# 220V-12V_Power_Interface.net
KiCad netlist of a schematic drawn in Altium Designer
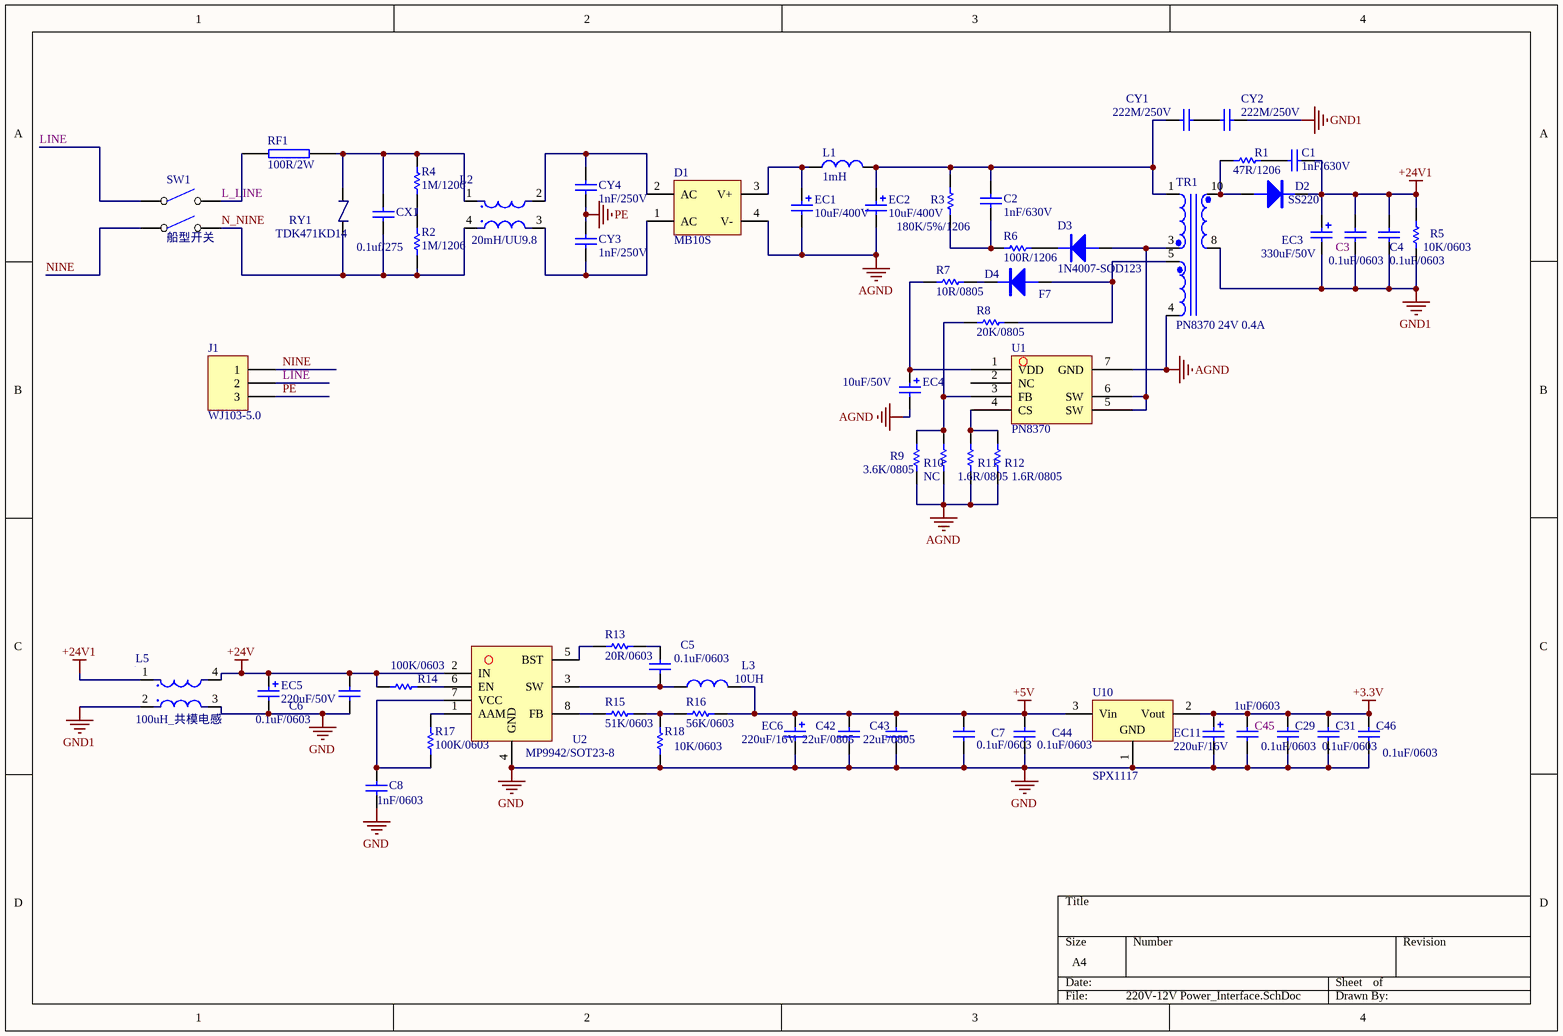
[diagram p0: 220V-12V Power_Interface.SchDoc]

(export (version "E")
  (design (tool "Eeschema 10.0.6"))
  (components
    (comp (ref "C1")
      (value "1nF/630V")
      (footprint "CAP/SMT/1206C")
      (libsource (lib "Menred_原理图 封装库") (part "CAP/CAP/SMT/1206C"))
    )
    (comp (ref "C2")
      (value "1nF/630V")
      (footprint "CAP/SMT/1206C")
      (libsource (lib "Menred_原理图 封装库") (part "CAP/CAP/SMT/1206C"))
    )
    (comp (ref "C3")
      (value "0.1uF/0603")
      (footprint "CAP/SMT/0603C")
      (libsource (lib "Menred_原理图 封装库") (part "CAP/CAP/SMT/0603C"))
    )
    (comp (ref "C4")
      (value "0.1uF/0603")
      (footprint "CAP/SMT/0603C")
      (libsource (lib "Menred_原理图 封装库") (part "CAP/CAP/SMT/0603C"))
    )
    (comp (ref "C5")
      (value "0.1uF/0603")
      (footprint "CAP/SMT/0603C")
      (libsource (lib "Menred_原理图 封装库") (part "CAP/CAP/SMT/0603C"))
    )
    (comp (ref "C6")
      (value "0.1uF/0603")
      (footprint "CAP/SMT/0603C")
      (libsource (lib "Menred_原理图 封装库") (part "CAP/CAP/SMT/0603C"))
    )
    (comp (ref "C7")
      (value "0.1uF/0603")
      (footprint "CAP/SMT/0603C")
      (libsource (lib "Menred_原理图 封装库") (part "CAP/CAP/SMT/0603C"))
    )
    (comp (ref "C8")
      (value "1nF/0603")
      (footprint "CAP/SMT/0603C")
      (libsource (lib "Menred_原理图 封装库") (part "CAP/CAP/SMT/0603C"))
    )
    (comp (ref "C29")
      (value "0.1uF/0603")
      (footprint "CAP/SMT/0603C")
      (libsource (lib "Menred_原理图 封装库") (part "CAP/CAP/SMT/0603C"))
    )
    (comp (ref "C31")
      (value "0.1uF/0603")
      (footprint "CAP/SMT/0603C")
      (libsource (lib "Menred_原理图 封装库") (part "CAP/CAP/SMT/0603C"))
    )
    (comp (ref "C42")
      (value "22uF/0805")
      (footprint "CAP/SMT/0805C")
      (libsource (lib "Menred_原理图 封装库") (part "CAP/CAP/SMT/0805C"))
    )
    (comp (ref "C43")
      (value "22uF/0805")
      (footprint "CAP/SMT/0805C")
      (libsource (lib "Menred_原理图 封装库") (part "CAP/CAP/SMT/0805C"))
    )
    (comp (ref "C44")
      (value "0.1uF/0603")
      (footprint "CAP/SMT/0603C")
      (libsource (lib "Menred_原理图 封装库") (part "CAP/CAP/SMT/0603C"))
    )
    (comp (ref "C45")
      (value "1uF/0603")
      (footprint "CAP/SMT/0603C")
      (libsource (lib "Menred_原理图 封装库") (part "CAP/CAP/SMT/0603C"))
    )
    (comp (ref "C46")
      (value "0.1uF/0603")
      (footprint "CAP/SMT/0603C")
      (libsource (lib "Menred_原理图 封装库") (part "CAP/CAP/SMT/0603C"))
    )
    (comp (ref "CX1")
      (value "0.1uf/275")
      (footprint "CAP/DIP/0.1uF/250V")
      (libsource (lib "Menred_原理图 封装库") (part "CAP/DIP/0.1uF/275V"))
    )
    (comp (ref "CY1")
      (value "222M/250V")
      (footprint "CAP/DIP/102M/250V")
      (libsource (lib "Menred_原理图 封装库") (part "CAP/DIP/102M/250V"))
    )
    (comp (ref "CY2")
      (value "222M/250V")
      (footprint "CAP/DIP/102M/250V")
      (libsource (lib "Menred_原理图 封装库") (part "CAP/DIP/102M/250V"))
    )
    (comp (ref "CY3")
      (value "1nF/250V")
      (footprint "CAP/DIP/102M/250V")
      (libsource (lib "Menred_原理图 封装库") (part "CAP/DIP/102M/250V"))
    )
    (comp (ref "CY4")
      (value "1nF/250V")
      (footprint "CAP/DIP/102M/250V")
      (libsource (lib "Menred_原理图 封装库") (part "CAP/DIP/102M/250V"))
    )
    (comp (ref "D1")
      (value "MB10S")
      (footprint "D/SMT/MD6S-TR")
      (description "D_Bridge")
      (libsource (lib "Menred_原理图 封装库") (part "D/BRIDGE/SMT/MB10S"))
    )
    (comp (ref "D2")
      (value "SS220")
      (footprint "D/SMT/DO-214AC")
      (libsource (lib "Menred_原理图 封装库") (part "D/D/SMT/SS210/DO-214"))
    )
    (comp (ref "D3")
      (value "1N4007-SOD123")
      (footprint "D/SMT/SOD123")
      (libsource (lib "Menred_原理图 封装库") (part "D/D/SMT/1N4007-SOD123"))
    )
    (comp (ref "D4")
      (value "F7")
      (footprint "D/SMT/DO-214AC")
      (libsource (lib "Menred_原理图 封装库") (part "D/D/SMT/FFM107/DO-214"))
    )
    (comp (ref "EC1")
      (value "10uF/400V")
      (footprint "CAP/DIP/6.8UF/400V/10MM")
      (libsource (lib "电容类器件") (part "CAP/AEC/DIP/6.8uF/400V"))
    )
    (comp (ref "EC2")
      (value "10uF/400V")
      (footprint "CAP/DIP/6.8UF/400V/10MM")
      (libsource (lib "电容类器件") (part "CAP/AEC/DIP/6.8uF/400V"))
    )
    (comp (ref "EC3")
      (value "330uF/50V")
      (footprint "CAP/SMT/220UF/50V")
      (libsource (lib "Menred_原理图 封装库") (part "CAP/AEC/DIP/330uF/25V"))
    )
    (comp (ref "EC4")
      (value "10uF/50V")
      (footprint "CAP/DIP/10uF/50V")
      (libsource (lib "电容类器件") (part "CAP/AEC/DIP/10uF/50V"))
    )
    (comp (ref "EC5")
      (value "220uF/50V")
      (footprint "CAP/SMT/220UF/50V")
      (libsource (lib "Menred_原理图 封装库") (part "CAP/AEC/SMT/220uF/50V"))
    )
    (comp (ref "EC6")
      (value "220uF/16V")
      (footprint "CAP/SMT/220UF/16V")
      (libsource (lib "Menred_原理图 封装库") (part "CAP/AEC/SMT/220uF/16V"))
    )
    (comp (ref "EC11")
      (value "220uF/16V")
      (footprint "CAP/SMT/100UF/25V")
      (libsource (lib "Menred_原理图 封装库") (part "CAP/AEC/SMT/100uF/25V"))
    )
    (comp (ref "J1")
      (value "WJ103-5.0")
      (footprint "CON/DIP/1×3PIN/5.0MM/WJ103-3P")
      (description "Connector")
      (libsource (lib "Menred_原理图 封装库") (part "CON/DIP/1X3PIN/WJ103-5.0MM"))
    )
    (comp (ref "L1")
      (value "1mH")
      (footprint "L/DIP/1mH")
      (description "工字电感")
      (libsource (lib "Menred_原理图 封装库") (part "L/L/DIP/JYGX68-1.0mH/300mA"))
    )
    (comp (ref "L2")
      (value "20mH/UU9.8")
      (footprint "L/DIP/20mH/UU9.8")
      (description "共模电感")
      (libsource (lib "Menred_原理图 封装库") (part "L/L/DIP/20mH"))
    )
    (comp (ref "L3")
      (value "10UH")
      (footprint "L/SMT/SWPA3015S150MT")
      (description "电感3.0MM*3.0MM*1.5MM")
      (libsource (lib "Menred_原理图 封装库") (part "L/L/SMT/SWPA3015S150MT"))
    )
    (comp (ref "L5")
      (value "100uH_共模电感")
      (footprint "L/DIP/500uH")
      (description "共模电感")
      (libsource (lib "Menred_原理图 封装库") (part "L/L/DIP/100uH_共模电感"))
    )
    (comp (ref "R1")
      (value "47R/1206")
      (footprint "1206R")
      (libsource (lib "Menred_原理图 封装库") (part "RES/RES/SMT/1206"))
    )
    (comp (ref "R2")
      (value "1M/1206")
      (footprint "1206R")
      (libsource (lib "Menred_原理图 封装库") (part "RES/RES/SMT/1206"))
    )
    (comp (ref "R3")
      (value "180K/5%/1206")
      (footprint "1206R")
      (libsource (lib "Menred_原理图 封装库") (part "RES/RES/SMT/1206"))
    )
    (comp (ref "R4")
      (value "1M/1206")
      (footprint "1206R")
      (libsource (lib "Menred_原理图 封装库") (part "RES/RES/SMT/1206"))
    )
    (comp (ref "R5")
      (value "10K/0603")
      (footprint "0603R")
      (libsource (lib "Menred_原理图 封装库") (part "RES/RES/SMT/0603"))
    )
    (comp (ref "R6")
      (value "100R/1206")
      (footprint "1206R")
      (libsource (lib "Menred_原理图 封装库") (part "RES/RES/SMT/1206"))
    )
    (comp (ref "R7")
      (value "10R/0805")
      (footprint "0805R")
      (libsource (lib "Menred_原理图 封装库") (part "RES/RES/SMT/0805"))
    )
    (comp (ref "R8")
      (value "20K/0805")
      (footprint "0805R")
      (libsource (lib "Menred_原理图 封装库") (part "RES/RES/SMT/0805"))
    )
    (comp (ref "R9")
      (value "3.6K/0805")
      (footprint "0805R")
      (libsource (lib "Menred_原理图 封装库") (part "RES/RES/SMT/0805"))
    )
    (comp (ref "R10")
      (value "NC")
      (footprint "0805R")
      (libsource (lib "Menred_原理图 封装库") (part "RES/RES/SMT/0805"))
    )
    (comp (ref "R11")
      (value "1.6R/0805")
      (footprint "0805R")
      (libsource (lib "Menred_原理图 封装库") (part "RES/RES/SMT/0805"))
    )
    (comp (ref "R12")
      (value "1.6R/0805")
      (footprint "0805R")
      (libsource (lib "Menred_原理图 封装库") (part "RES/RES/SMT/0805"))
    )
    (comp (ref "R13")
      (value "20R/0603")
      (footprint "0603R")
      (libsource (lib "Menred_原理图 封装库") (part "RES/RES/SMT/0603"))
    )
    (comp (ref "R14")
      (value "100K/0603")
      (footprint "0603R")
      (libsource (lib "Menred_原理图 封装库") (part "RES/RES/SMT/0603"))
    )
    (comp (ref "R15")
      (value "51K/0603")
      (footprint "0603R")
      (libsource (lib "Menred_原理图 封装库") (part "RES/RES/SMT/0603"))
    )
    (comp (ref "R16")
      (value "56K/0603")
      (footprint "0603R")
      (libsource (lib "Menred_原理图 封装库") (part "RES/RES/SMT/0603"))
    )
    (comp (ref "R17")
      (value "100K/0603")
      (footprint "0603R")
      (libsource (lib "Menred_原理图 封装库") (part "RES/RES/SMT/0603"))
    )
    (comp (ref "R18")
      (value "10K/0603")
      (footprint "0603R")
      (libsource (lib "Menred_原理图 封装库") (part "RES/RES/SMT/0603"))
    )
    (comp (ref "RF1")
      (value "100R/2W")
      (footprint "FUSE/3.15A")
      (libsource (lib "Menred_原理图 封装库") (part "FUSE/FUSE/DIP/3.15A"))
    )
    (comp (ref "RY1")
      (value "TDK471KD14")
      (footprint "RES/RY/TDK471KD14")
      (libsource (lib "Menred_原理图 封装库") (part "RES/RY/DIP/TDK471KD14"))
    )
    (comp (ref "SW1")
      (value "船型开关")
      (footprint "DIP4 - duplicate")
      (libsource (lib "Menred_原理图 封装库") (part "SWITCH/POWER/DIP/船型开关"))
    )
    (comp (ref "TR1")
      (value "PN8370 24V 0.4A")
      (footprint "L/TRANS/DIP/PN8370 24V 0.4A")
      (libsource (lib "Menred_原理图 封装库") (part "L/TRANS/DIP/PN8370 24V 0.4A"))
    )
    (comp (ref "U1")
      (value "PN8370")
      (footprint "SOP-7")
      (libsource (lib "Menred_原理图 封装库") (part "IC/POWER/SMT/PN8366/SOP-8"))
    )
    (comp (ref "U2")
      (value "MP9942/SOT23-8")
      (footprint "TSOT-8")
      (libsource (lib "集成芯片类") (part "IC/POWER/SMT/MPS2314/SOT23-8"))
    )
    (comp (ref "U10")
      (value "SPX1117")
      (footprint "SOT-223")
      (fields (field (name "MANUFACTURER") "Generic Components"))
      (libsource (lib "Menred_原理图 封装库") (part "IC/POWER/SMT/SPX1117M3-L3.3TR/SOT-223"))
    )
  )
  (nets
    (net (code "1") (name "+3.3V") (class "Default")
      (node (ref "C29") (pin "2") (pinfunction "2_2") (pintype "passive"))
      (node (ref "C31") (pin "2") (pinfunction "2_2") (pintype "passive"))
      (node (ref "C45") (pin "2") (pinfunction "2_2") (pintype "passive"))
      (node (ref "C46") (pin "2") (pinfunction "2_2") (pintype "passive"))
      (node (ref "EC11") (pin "1") (pinfunction "1_1") (pintype "passive"))
      (node (ref "U10") (pin "2") (pinfunction "Vout_2") (pintype "passive"))
    )
    (net (code "2") (name "+5V") (class "Default")
      (node (ref "C42") (pin "2") (pinfunction "2_2") (pintype "passive"))
      (node (ref "C43") (pin "2") (pinfunction "2_2") (pintype "passive"))
      (node (ref "C44") (pin "2") (pinfunction "2_2") (pintype "passive"))
      (node (ref "C7") (pin "2") (pinfunction "2_2") (pintype "passive"))
      (node (ref "EC6") (pin "1") (pinfunction "1_1") (pintype "passive"))
      (node (ref "L3") (pin "2") (pinfunction "2_2") (pintype "passive"))
      (node (ref "R16") (pin "2") (pinfunction "2_2") (pintype "passive"))
      (node (ref "U10") (pin "3") (pinfunction "Vin_3") (pintype "passive"))
    )
    (net (code "3") (name "+24V") (class "Default")
      (node (ref "C6") (pin "1") (pinfunction "1_1") (pintype "passive"))
      (node (ref "EC5") (pin "1") (pinfunction "1_1") (pintype "passive"))
      (node (ref "L5") (pin "4") (pinfunction "4_4") (pintype "passive"))
      (node (ref "R14") (pin "1") (pinfunction "1_1") (pintype "passive"))
      (node (ref "U2") (pin "2") (pinfunction "IN_2") (pintype "passive"))
    )
    (net (code "4") (name "+24V1") (class "Default")
      (node (ref "C1") (pin "2") (pinfunction "2_2") (pintype "passive"))
      (node (ref "C3") (pin "1") (pinfunction "1_1") (pintype "passive"))
      (node (ref "C4") (pin "1") (pinfunction "1_1") (pintype "passive"))
      (node (ref "D2") (pin "1") (pinfunction "K_1") (pintype "passive"))
      (node (ref "EC3") (pin "1") (pinfunction "1_1") (pintype "passive"))
      (node (ref "L5") (pin "1") (pinfunction "1_1") (pintype "passive"))
      (node (ref "R5") (pin "2") (pinfunction "2_2") (pintype "passive"))
    )
    (net (code "5") (name "/LINE") (class "Default")
      (node (ref "J1") (pin "2") (pinfunction "2_2") (pintype "passive"))
      (node (ref "SW1") (pin "2") (pinfunction "2_2") (pintype "passive"))
    )
    (net (code "6") (name "/L_LINE") (class "Default")
      (node (ref "RF1") (pin "2") (pinfunction "2_2") (pintype "passive"))
      (node (ref "SW1") (pin "1") (pinfunction "1_1") (pintype "passive"))
    )
    (net (code "7") (name "/NINE") (class "Default")
      (node (ref "J1") (pin "1") (pinfunction "1_1") (pintype "passive"))
      (node (ref "SW1") (pin "4") (pinfunction "4_4") (pintype "passive"))
    )
    (net (code "8") (name "/N_NINE") (class "Default")
      (node (ref "CX1") (pin "2") (pinfunction "2_2") (pintype "passive"))
      (node (ref "L2") (pin "4") (pinfunction "4_4") (pintype "passive"))
      (node (ref "R2") (pin "1") (pinfunction "1_1") (pintype "passive"))
      (node (ref "RY1") (pin "1") (pinfunction "1_1") (pintype "passive"))
      (node (ref "SW1") (pin "3") (pinfunction "3_3") (pintype "passive"))
    )
    (net (code "9") (name "AGND") (class "Default")
      (node (ref "D1") (pin "4") (pinfunction "V-_4") (pintype "passive"))
      (node (ref "EC1") (pin "2") (pinfunction "2_2") (pintype "passive"))
      (node (ref "EC2") (pin "2") (pinfunction "2_2") (pintype "passive"))
      (node (ref "EC4") (pin "2") (pinfunction "2_2") (pintype "passive"))
      (node (ref "R10") (pin "1") (pinfunction "1_1") (pintype "passive"))
      (node (ref "R11") (pin "1") (pinfunction "1_1") (pintype "passive"))
      (node (ref "R12") (pin "1") (pinfunction "1_1") (pintype "passive"))
      (node (ref "R9") (pin "1") (pinfunction "1_1") (pintype "passive"))
      (node (ref "TR1") (pin "4") (pintype "passive"))
      (node (ref "U1") (pin "7") (pinfunction "GND_7") (pintype "passive"))
    )
    (net (code "10") (name "GND") (class "Default")
      (node (ref "C29") (pin "1") (pinfunction "1_1") (pintype "passive"))
      (node (ref "C31") (pin "1") (pinfunction "1_1") (pintype "passive"))
      (node (ref "C42") (pin "1") (pinfunction "1_1") (pintype "passive"))
      (node (ref "C43") (pin "1") (pinfunction "1_1") (pintype "passive"))
      (node (ref "C44") (pin "1") (pinfunction "1_1") (pintype "passive"))
      (node (ref "C45") (pin "1") (pinfunction "1_1") (pintype "passive"))
      (node (ref "C46") (pin "1") (pinfunction "1_1") (pintype "passive"))
      (node (ref "C6") (pin "2") (pinfunction "2_2") (pintype "passive"))
      (node (ref "C7") (pin "1") (pinfunction "1_1") (pintype "passive"))
      (node (ref "C8") (pin "2") (pinfunction "2_2") (pintype "passive"))
      (node (ref "EC11") (pin "2") (pinfunction "2_2") (pintype "passive"))
      (node (ref "EC5") (pin "2") (pinfunction "2_2") (pintype "passive"))
      (node (ref "EC6") (pin "2") (pinfunction "2_2") (pintype "passive"))
      (node (ref "L5") (pin "3") (pinfunction "3_3") (pintype "passive"))
      (node (ref "R18") (pin "2") (pinfunction "2_2") (pintype "passive"))
      (node (ref "U10") (pin "1") (pinfunction "GND_1") (pintype "passive"))
      (node (ref "U2") (pin "4") (pinfunction "GND_4") (pintype "passive"))
    )
    (net (code "11") (name "GND1") (class "Default")
      (node (ref "C3") (pin "2") (pinfunction "2_2") (pintype "passive"))
      (node (ref "C4") (pin "2") (pinfunction "2_2") (pintype "passive"))
      (node (ref "CY2") (pin "2") (pinfunction "2_2") (pintype "passive"))
      (node (ref "EC3") (pin "2") (pinfunction "2_2") (pintype "passive"))
      (node (ref "L5") (pin "2") (pinfunction "2_2") (pintype "passive"))
      (node (ref "R5") (pin "1") (pinfunction "1_1") (pintype "passive"))
      (node (ref "TR1") (pin "8") (pintype "passive"))
    )
    (net (code "12") (name "Net-(C1-Pad1)") (class "Default")
      (node (ref "C1") (pin "1") (pinfunction "1_1") (pintype "passive"))
      (node (ref "R1") (pin "2") (pinfunction "2_2") (pintype "passive"))
    )
    (net (code "13") (name "Net-(C2-Pad1)") (class "Default")
      (node (ref "C2") (pin "1") (pinfunction "1_1") (pintype "passive"))
      (node (ref "R3") (pin "1") (pinfunction "1_1") (pintype "passive"))
      (node (ref "R6") (pin "2") (pinfunction "2_2") (pintype "passive"))
    )
    (net (code "14") (name "Net-(C2-Pad2)") (class "Default")
      (node (ref "C2") (pin "2") (pinfunction "2_2") (pintype "passive"))
      (node (ref "CY1") (pin "1") (pinfunction "1_1") (pintype "passive"))
      (node (ref "EC2") (pin "1") (pinfunction "1_1") (pintype "passive"))
      (node (ref "L1") (pin "2") (pinfunction "2_2") (pintype "passive"))
      (node (ref "R3") (pin "2") (pinfunction "2_2") (pintype "passive"))
      (node (ref "TR1") (pin "1") (pintype "passive"))
    )
    (net (code "15") (name "Net-(C5-Pad1)") (class "Default")
      (node (ref "C5") (pin "1") (pinfunction "1_1") (pintype "passive"))
      (node (ref "R13") (pin "1") (pinfunction "1_1") (pintype "passive"))
    )
    (net (code "16") (name "Net-(CX1-Pad1)") (class "Default")
      (node (ref "CX1") (pin "1") (pinfunction "1_1") (pintype "passive"))
      (node (ref "L2") (pin "1") (pinfunction "1_1") (pintype "passive"))
      (node (ref "R4") (pin "2") (pinfunction "2_2") (pintype "passive"))
      (node (ref "RF1") (pin "1") (pinfunction "1_1") (pintype "passive"))
      (node (ref "RY1") (pin "2") (pinfunction "2_2") (pintype "passive"))
    )
    (net (code "17") (name "Net-(CY1-Pad2)") (class "Default")
      (node (ref "CY1") (pin "2") (pinfunction "2_2") (pintype "passive"))
      (node (ref "CY2") (pin "1") (pinfunction "1_1") (pintype "passive"))
    )
    (net (code "18") (name "Net-(CY3-Pad2)") (class "Default")
      (node (ref "CY3") (pin "2") (pinfunction "2_2") (pintype "passive"))
      (node (ref "D1") (pin "1") (pinfunction "AC_1") (pintype "passive"))
      (node (ref "L2") (pin "3") (pinfunction "3_3") (pintype "passive"))
    )
    (net (code "19") (name "Net-(CY4-Pad1)") (class "Default")
      (node (ref "CY4") (pin "1") (pinfunction "1_1") (pintype "passive"))
      (node (ref "D1") (pin "2") (pinfunction "AC_2") (pintype "passive"))
      (node (ref "L2") (pin "2") (pinfunction "2_2") (pintype "passive"))
    )
    (net (code "20") (name "Net-(D1-V+)") (class "Default")
      (node (ref "D1") (pin "3") (pinfunction "V+_3") (pintype "passive"))
      (node (ref "EC1") (pin "1") (pinfunction "1_1") (pintype "passive"))
      (node (ref "L1") (pin "1") (pinfunction "1_1") (pintype "passive"))
    )
    (net (code "21") (name "Net-(D2-A)") (class "Default")
      (node (ref "D2") (pin "2") (pinfunction "A_2") (pintype "passive"))
      (node (ref "R1") (pin "1") (pinfunction "1_1") (pintype "passive"))
      (node (ref "TR1") (pin "10") (pintype "passive"))
    )
    (net (code "22") (name "Net-(D3-A)") (class "Default")
      (node (ref "D3") (pin "2") (pinfunction "A_2") (pintype "passive"))
      (node (ref "TR1") (pin "3") (pintype "passive"))
      (node (ref "U1") (pin "5") (pinfunction "SW_5") (pintype "passive"))
      (node (ref "U1") (pin "6") (pinfunction "SW_6") (pintype "passive"))
    )
    (net (code "23") (name "Net-(D3-K)") (class "Default")
      (node (ref "D3") (pin "1") (pinfunction "K_1") (pintype "passive"))
      (node (ref "R6") (pin "1") (pinfunction "1_1") (pintype "passive"))
    )
    (net (code "24") (name "Net-(D4-A)") (class "Default")
      (node (ref "D4") (pin "2") (pinfunction "A_2") (pintype "passive"))
      (node (ref "R8") (pin "2") (pinfunction "2_2") (pintype "passive"))
      (node (ref "TR1") (pin "5") (pintype "passive"))
    )
    (net (code "25") (name "Net-(D4-K)") (class "Default")
      (node (ref "D4") (pin "1") (pinfunction "K_1") (pintype "passive"))
      (node (ref "R7") (pin "2") (pinfunction "2_2") (pintype "passive"))
    )
    (net (code "26") (name "Net-(R2-Pad2)") (class "Default")
      (node (ref "R2") (pin "2") (pinfunction "2_2") (pintype "passive"))
      (node (ref "R4") (pin "1") (pinfunction "1_1") (pintype "passive"))
    )
    (net (code "27") (name "Net-(R15-Pad2)") (class "Default")
      (node (ref "R15") (pin "2") (pinfunction "2_2") (pintype "passive"))
      (node (ref "R16") (pin "1") (pinfunction "1_1") (pintype "passive"))
      (node (ref "R18") (pin "1") (pinfunction "1_1") (pintype "passive"))
    )
    (net (code "28") (name "Net-(U1-CS)") (class "Default")
      (node (ref "R11") (pin "2") (pinfunction "2_2") (pintype "passive"))
      (node (ref "R12") (pin "2") (pinfunction "2_2") (pintype "passive"))
      (node (ref "U1") (pin "4") (pinfunction "CS_4") (pintype "passive"))
    )
    (net (code "29") (name "Net-(U1-FB)") (class "Default")
      (node (ref "R10") (pin "2") (pinfunction "2_2") (pintype "passive"))
      (node (ref "R8") (pin "1") (pinfunction "1_1") (pintype "passive"))
      (node (ref "R9") (pin "2") (pinfunction "2_2") (pintype "passive"))
      (node (ref "U1") (pin "3") (pinfunction "FB_3") (pintype "passive"))
    )
    (net (code "30") (name "Net-(U1-VDD)") (class "Default")
      (node (ref "EC4") (pin "1") (pinfunction "1_1") (pintype "passive"))
      (node (ref "R7") (pin "1") (pinfunction "1_1") (pintype "passive"))
      (node (ref "U1") (pin "1") (pinfunction "VDD_1") (pintype "passive"))
    )
    (net (code "31") (name "Net-(U2-AAM)") (class "Default")
      (node (ref "R17") (pin "2") (pinfunction "2_2") (pintype "passive"))
      (node (ref "U2") (pin "1") (pinfunction "AAM_1") (pintype "passive"))
    )
    (net (code "32") (name "Net-(U2-BST)") (class "Default")
      (node (ref "R13") (pin "2") (pinfunction "2_2") (pintype "passive"))
      (node (ref "U2") (pin "5") (pinfunction "BST_5") (pintype "passive"))
    )
    (net (code "33") (name "Net-(U2-EN)") (class "Default")
      (node (ref "R14") (pin "2") (pinfunction "2_2") (pintype "passive"))
      (node (ref "U2") (pin "6") (pinfunction "EN_6") (pintype "passive"))
    )
    (net (code "34") (name "Net-(U2-FB)") (class "Default")
      (node (ref "R15") (pin "1") (pinfunction "1_1") (pintype "passive"))
      (node (ref "U2") (pin "8") (pinfunction "FB_8") (pintype "passive"))
    )
    (net (code "35") (name "Net-(U2-SW)") (class "Default")
      (node (ref "C5") (pin "2") (pinfunction "2_2") (pintype "passive"))
      (node (ref "L3") (pin "1") (pinfunction "1_1") (pintype "passive"))
      (node (ref "U2") (pin "3") (pinfunction "SW_3") (pintype "passive"))
    )
    (net (code "36") (name "Net-(U2-VCC)") (class "Default")
      (node (ref "C8") (pin "1") (pinfunction "1_1") (pintype "passive"))
      (node (ref "R17") (pin "1") (pinfunction "1_1") (pintype "passive"))
      (node (ref "U2") (pin "7") (pinfunction "VCC_7") (pintype "passive"))
    )
    (net (code "37") (name "PE") (class "Default")
      (node (ref "CY3") (pin "1") (pinfunction "1_1") (pintype "passive"))
      (node (ref "CY4") (pin "2") (pinfunction "2_2") (pintype "passive"))
      (node (ref "J1") (pin "3") (pinfunction "3_3") (pintype "passive"))
    )
    (net (code "38") (name "unconnected-(U1-NC-Pad2)") (class "Default")
      (node (ref "U1") (pin "2") (pinfunction "NC_2") (pintype "passive"))
    )
  )
)
